# lidar4_sch.net
KiCad netlist of a schematic drawn in Altium Designer
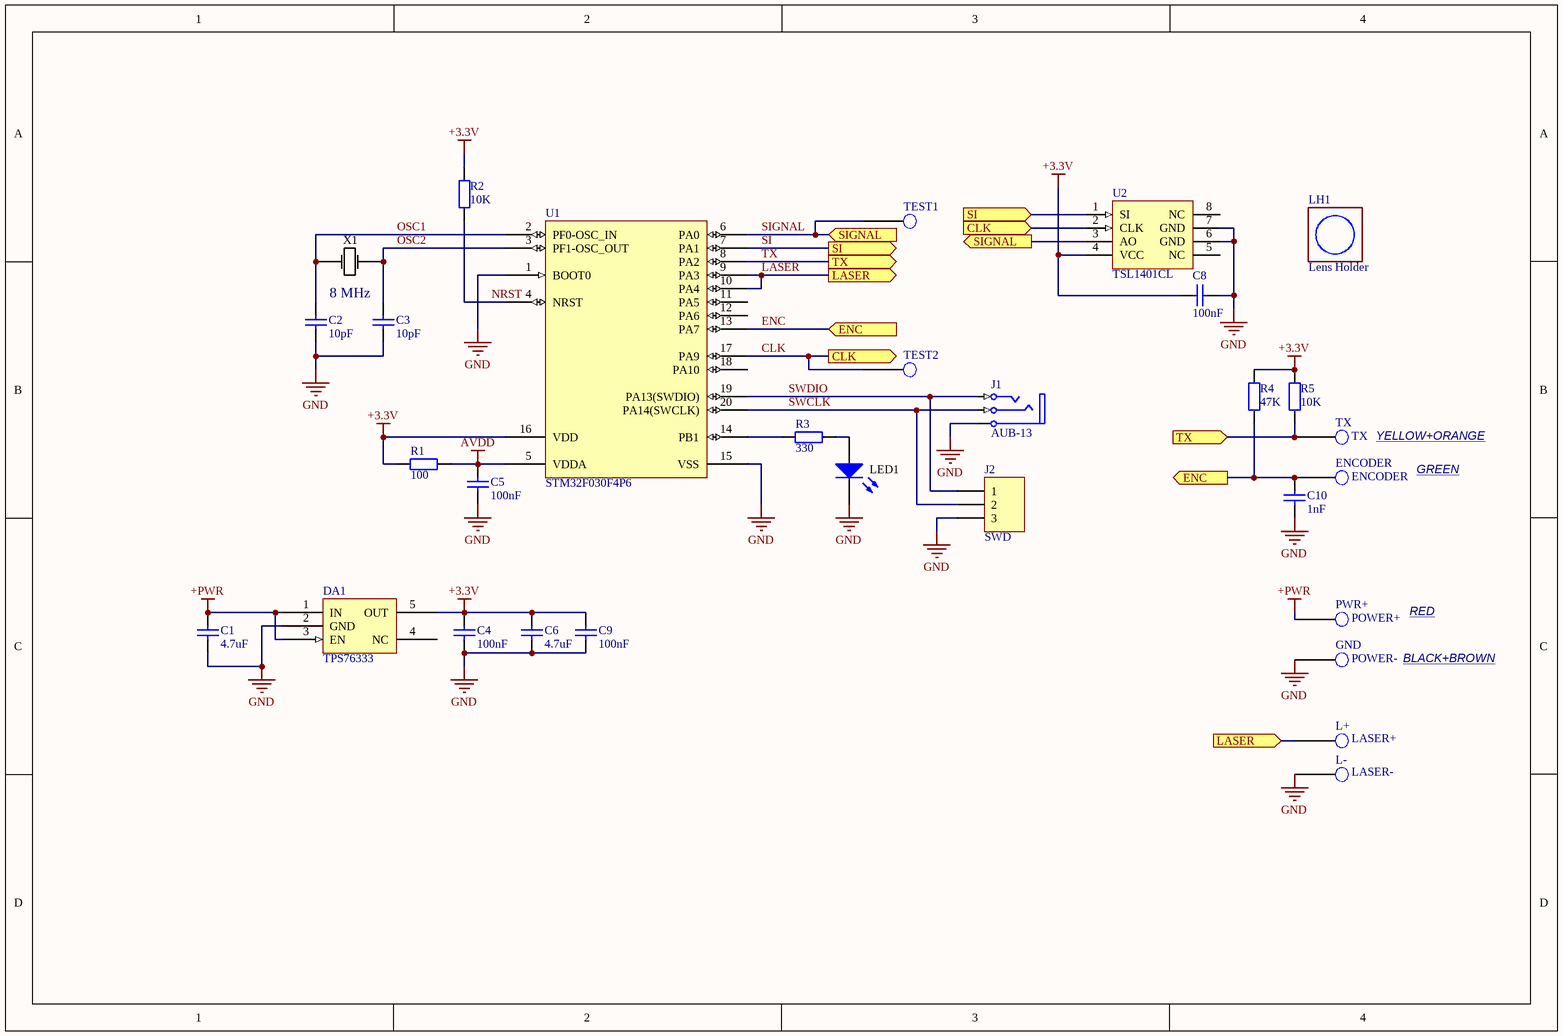
[diagram p0: lidar4_sch.SchDoc]

(export (version "E")
  (design (tool "Eeschema 10.0.6"))
  (components
    (comp (ref "C1")
      (value "4.7uF")
      (footprint "CAPC2012X135N")
      (description "Chip capacitor")
      (fields (field (name "VOLTAGE") "25V"))
      (libsource (lib "MyLibSch") (part "CC0805"))
    )
    (comp (ref "C2")
      (value "10pF")
      (footprint "CAPC1608X90N")
      (description "Chip capacitor")
      (fields (field (name "VOLTAGE") "25V"))
      (libsource (lib "MyLibSch") (part "CC0805"))
    )
    (comp (ref "C3")
      (value "10pF")
      (footprint "CAPC1608X90N")
      (description "Chip capacitor")
      (fields (field (name "VOLTAGE") "25V"))
      (libsource (lib "MyLibSch") (part "CC0805"))
    )
    (comp (ref "C4")
      (value "100nF")
      (footprint "CAPC1608X90N")
      (description "Chip capacitor")
      (fields (field (name "VOLTAGE") "25V"))
      (libsource (lib "MyLibSch") (part "CC0805"))
    )
    (comp (ref "C5")
      (value "100nF")
      (footprint "CAPC1608X90N")
      (description "Chip capacitor")
      (fields (field (name "VOLTAGE") "25V"))
      (libsource (lib "MyLibSch") (part "CC0805"))
    )
    (comp (ref "C6")
      (value "4.7uF")
      (footprint "CAPC2012X135N")
      (description "Chip capacitor")
      (fields (field (name "VOLTAGE") "25V"))
      (libsource (lib "MyLibSch") (part "CC0805"))
    )
    (comp (ref "C8")
      (value "100nF")
      (footprint "CAPC1608X90N")
      (description "Chip capacitor")
      (fields (field (name "VOLTAGE") "25V"))
      (libsource (lib "MyLibSch") (part "CC0805"))
    )
    (comp (ref "C9")
      (value "100nF")
      (footprint "CAPC1608X90N")
      (description "Chip capacitor")
      (fields (field (name "VOLTAGE") "25V"))
      (libsource (lib "MyLibSch") (part "CC0805"))
    )
    (comp (ref "C10")
      (value "1nF")
      (footprint "CAPC1608X90N")
      (description "Chip capacitor")
      (fields (field (name "VOLTAGE") "25V"))
      (libsource (lib "MyLibSch") (part "CC0805"))
    )
    (comp (ref "DA1")
      (value "TPS76333")
      (footprint "SOT23-5")
      (description "LDO")
      (libsource (lib "lcd_lib") (part "TPS76333"))
    )
    (comp (ref "ENCODER")
      (value "ENCODER")
      (footprint "Ext_pad")
      (description "Pad for wire")
      (libsource (lib "lcd_lib") (part "Ext Pad"))
    )
    (comp (ref "GND")
      (value "POWER-")
      (footprint "Ext_pad")
      (description "Pad for wire")
      (libsource (lib "lcd_lib") (part "Ext Pad"))
    )
    (comp (ref "J1")
      (value "AUB-13")
      (footprint "AUB-13")
      (description "Jack Socket, 1/4\" [6.5mm], Thru-Hole, Vertical, 3-Conductor Open Circuit (Non-Normalling)")
      (fields (field (name "PUBLISHER") "Altium Limited"))
      (libsource (lib "Miscellaneous Connectors") (part "Phonejack3"))
    )
    (comp (ref "J2")
      (value "SWD")
      (footprint "HDR1X3")
      (description "Header, 3-Pin")
      (fields (field (name "PUBLISHER") "Altium Limited"))
      (libsource (lib "Miscellaneous Connectors") (part "Header 3"))
    )
    (comp (ref "L+")
      (value "LASER+")
      (footprint "Ext_hole")
      (description "Pad for wire")
      (libsource (lib "lcd_lib") (part "Ext Pad"))
    )
    (comp (ref "L-")
      (value "LASER-")
      (footprint "Ext_hole")
      (description "Pad for wire")
      (libsource (lib "lcd_lib") (part "Ext Pad"))
    )
    (comp (ref "LED1")
      (value "LED")
      (footprint "PcbLib3:LED_0603")
      (description "LED_0603")
      (libsource (lib "lcd_lib") (part "LED_0603"))
    )
    (comp (ref "LH1")
      (value "Lens Holder")
      (footprint "LENS_HOLDER_2")
      (description "M12 Lens Holder")
      (libsource (lib "lcd_lib") (part "M12 Lens Holder"))
    )
    (comp (ref "PWR+")
      (value "POWER+")
      (footprint "Ext_pad")
      (description "Pad for wire")
      (libsource (lib "lcd_lib") (part "Ext Pad"))
    )
    (comp (ref "R1")
      (value "100")
      (footprint "RESC1608X55N")
      (description "Chip resistor")
      (fields (field (name "TOLERANCE") "5%"))
      (libsource (lib "") (part "RC0805_1"))
    )
    (comp (ref "R2")
      (value "10K")
      (footprint "RESC1608X55N")
      (description "Chip resistor")
      (fields (field (name "TOLERANCE") "5%"))
      (libsource (lib "MyLibSch") (part "RC0805"))
    )
    (comp (ref "R3")
      (value "330")
      (footprint "RESC1608X55N")
      (description "Chip resistor")
      (fields (field (name "TOLERANCE") "5%"))
      (libsource (lib "") (part "RC0805_2"))
    )
    (comp (ref "R4")
      (value "47K")
      (footprint "RESC1608X55N")
      (description "Chip resistor")
      (fields (field (name "TOLERANCE") "5%"))
      (libsource (lib "MyLibSch") (part "RC0805"))
    )
    (comp (ref "R5")
      (value "10K")
      (footprint "RESC1608X55N")
      (description "Chip resistor")
      (fields (field (name "TOLERANCE") "5%"))
      (libsource (lib "MyLibSch") (part "RC0805"))
    )
    (comp (ref "TEST1")
      (value "Pad")
      (footprint "PcbLib3:Ext_pad")
      (description "Pad for wire")
      (libsource (lib "lcd_lib") (part "Ext Pad"))
    )
    (comp (ref "TEST2")
      (value "Pad")
      (footprint "PcbLib3:Ext_pad")
      (description "Pad for wire")
      (libsource (lib "lcd_lib") (part "Ext Pad"))
    )
    (comp (ref "TX")
      (value "TX")
      (footprint "Ext_pad")
      (description "Pad for wire")
      (libsource (lib "lcd_lib") (part "Ext Pad"))
    )
    (comp (ref "U1")
      (value "STM32F030F4P6")
      (footprint "TSSOP65P640X120-20N")
      (libsource (lib "STM32 MCU") (part "STM32F030F4P6"))
    )
    (comp (ref "U2")
      (value "TSL1401CL")
      (footprint "PcbLib3:TSL1401CL_2")
      (description "Light sensor")
      (libsource (lib "lcd_lib") (part "TSL1401CL"))
    )
    (comp (ref "X1")
      (value "8 MHz")
      (footprint "SX-6 QUARTZ")
      (description "Quartz_SX-6 (SMD06035C4)")
      (fields (field (name "Comment") "Quartz"))
      (libsource (lib "lcd_lib") (part "Quartz_SX-6"))
    )
  )
  (nets
    (net (code "1") (name "+3.3V") (class "Default")
      (node (ref "C4") (pin "2") (pinfunction "2_2") (pintype "passive"))
      (node (ref "C6") (pin "2") (pinfunction "2_2") (pintype "passive"))
      (node (ref "C8") (pin "2") (pinfunction "2_2") (pintype "passive"))
      (node (ref "C9") (pin "2") (pinfunction "2_2") (pintype "passive"))
      (node (ref "DA1") (pin "5") (pinfunction "OUT_5") (pintype "passive"))
      (node (ref "R1") (pin "1") (pinfunction "1_1") (pintype "passive"))
      (node (ref "R2") (pin "1") (pinfunction "1_1") (pintype "passive"))
      (node (ref "R4") (pin "1") (pinfunction "1_1") (pintype "passive"))
      (node (ref "R5") (pin "1") (pinfunction "1_1") (pintype "passive"))
      (node (ref "U1") (pin "16") (pinfunction "VDD_16") (pintype "power_in"))
      (node (ref "U2") (pin "4") (pinfunction "VCC_4") (pintype "power_in"))
    )
    (net (code "2") (name "+PWR") (class "Default")
      (node (ref "C1") (pin "2") (pinfunction "2_2") (pintype "passive"))
      (node (ref "DA1") (pin "1") (pinfunction "IN_1") (pintype "power_in"))
      (node (ref "DA1") (pin "3") (pinfunction "EN_3") (pintype "input"))
      (node (ref "PWR+") (pin "1") (pinfunction "Pad_1") (pintype "passive"))
    )
    (net (code "3") (name "/CLK") (class "Default")
      (node (ref "TEST2") (pin "1") (pinfunction "Pad_1") (pintype "passive"))
      (node (ref "U1") (pin "17") (pinfunction "PA9_17") (pintype "bidirectional"))
      (node (ref "U2") (pin "2") (pinfunction "CLK_2") (pintype "input"))
    )
    (net (code "4") (name "/ENC") (class "Default")
      (node (ref "C10") (pin "2") (pinfunction "2_2") (pintype "passive"))
      (node (ref "ENCODER") (pin "1") (pinfunction "Pad_1") (pintype "passive"))
      (node (ref "R4") (pin "2") (pinfunction "2_2") (pintype "passive"))
      (node (ref "U1") (pin "13") (pinfunction "PA7_13") (pintype "bidirectional"))
    )
    (net (code "5") (name "/LASER") (class "Default")
      (node (ref "L+") (pin "1") (pinfunction "Pad_1") (pintype "passive"))
      (node (ref "U1") (pin "10") (pinfunction "PA4_10") (pintype "bidirectional"))
      (node (ref "U1") (pin "9") (pinfunction "PA3_9") (pintype "bidirectional"))
    )
    (net (code "6") (name "/NRST") (class "Default")
      (node (ref "R2") (pin "2") (pinfunction "2_2") (pintype "passive"))
      (node (ref "U1") (pin "4") (pinfunction "NRST_4") (pintype "bidirectional"))
    )
    (net (code "7") (name "/OSC1") (class "Default")
      (node (ref "C2") (pin "2") (pinfunction "2_2") (pintype "passive"))
      (node (ref "U1") (pin "2") (pinfunction "PF0-OSC_IN_2") (pintype "bidirectional"))
      (node (ref "X1") (pin "1") (pinfunction "1_1") (pintype "passive"))
    )
    (net (code "8") (name "/OSC2") (class "Default")
      (node (ref "C3") (pin "2") (pinfunction "2_2") (pintype "passive"))
      (node (ref "U1") (pin "3") (pinfunction "PF1-OSC_OUT_3") (pintype "bidirectional"))
      (node (ref "X1") (pin "3") (pinfunction "3_3") (pintype "passive"))
    )
    (net (code "9") (name "/SI") (class "Default")
      (node (ref "U1") (pin "7") (pinfunction "PA1_7") (pintype "bidirectional"))
      (node (ref "U2") (pin "1") (pinfunction "SI_1") (pintype "input"))
    )
    (net (code "10") (name "/SIGNAL") (class "Default")
      (node (ref "TEST1") (pin "1") (pinfunction "Pad_1") (pintype "passive"))
      (node (ref "U1") (pin "6") (pinfunction "PA0_6") (pintype "bidirectional"))
      (node (ref "U2") (pin "3") (pinfunction "AO_3") (pintype "passive"))
    )
    (net (code "11") (name "/SWCLK") (class "Default")
      (node (ref "J1") (pin "3") (pinfunction "R_3") (pintype "input"))
      (node (ref "J2") (pin "2") (pinfunction "2_2") (pintype "passive"))
      (node (ref "U1") (pin "20") (pinfunction "PA14(SWCLK)_20") (pintype "bidirectional"))
    )
    (net (code "12") (name "/SWDIO") (class "Default")
      (node (ref "J1") (pin "1") (pinfunction "T_1") (pintype "input"))
      (node (ref "J2") (pin "1") (pinfunction "1_1") (pintype "passive"))
      (node (ref "U1") (pin "19") (pinfunction "PA13(SWDIO)_19") (pintype "bidirectional"))
    )
    (net (code "13") (name "/TX") (class "Default")
      (node (ref "R5") (pin "2") (pinfunction "2_2") (pintype "passive"))
      (node (ref "TX") (pin "1") (pinfunction "Pad_1") (pintype "passive"))
      (node (ref "U1") (pin "8") (pinfunction "PA2_8") (pintype "bidirectional"))
    )
    (net (code "14") (name "AVDD") (class "Default")
      (node (ref "C5") (pin "2") (pinfunction "2_2") (pintype "passive"))
      (node (ref "R1") (pin "2") (pinfunction "2_2") (pintype "passive"))
      (node (ref "U1") (pin "5") (pinfunction "VDDA_5") (pintype "power_in"))
    )
    (net (code "15") (name "GND") (class "Default")
      (node (ref "C1") (pin "1") (pinfunction "1_1") (pintype "passive"))
      (node (ref "C10") (pin "1") (pinfunction "1_1") (pintype "passive"))
      (node (ref "C2") (pin "1") (pinfunction "1_1") (pintype "passive"))
      (node (ref "C3") (pin "1") (pinfunction "1_1") (pintype "passive"))
      (node (ref "C4") (pin "1") (pinfunction "1_1") (pintype "passive"))
      (node (ref "C5") (pin "1") (pinfunction "1_1") (pintype "passive"))
      (node (ref "C6") (pin "1") (pinfunction "1_1") (pintype "passive"))
      (node (ref "C8") (pin "1") (pinfunction "1_1") (pintype "passive"))
      (node (ref "C9") (pin "1") (pinfunction "1_1") (pintype "passive"))
      (node (ref "DA1") (pin "2") (pinfunction "GND_2") (pintype "power_in"))
      (node (ref "GND") (pin "1") (pinfunction "Pad_1") (pintype "passive"))
      (node (ref "J1") (pin "5") (pinfunction "S_5") (pintype "power_in"))
      (node (ref "J2") (pin "3") (pinfunction "3_3") (pintype "passive"))
      (node (ref "L-") (pin "1") (pinfunction "Pad_1") (pintype "passive"))
      (node (ref "LED1") (pin "2") (pinfunction "K_2") (pintype "passive"))
      (node (ref "U1") (pin "1") (pinfunction "BOOT0_1") (pintype "input"))
      (node (ref "U1") (pin "15") (pinfunction "VSS_15") (pintype "power_in"))
      (node (ref "U2") (pin "6") (pinfunction "GND_6") (pintype "power_in"))
      (node (ref "U2") (pin "7") (pinfunction "GND_7") (pintype "power_in"))
    )
    (net (code "16") (name "Net-(LED1-A)") (class "Default")
      (node (ref "LED1") (pin "1") (pinfunction "A_1") (pintype "passive"))
      (node (ref "R3") (pin "1") (pinfunction "1_1") (pintype "passive"))
    )
    (net (code "17") (name "Net-(U1-PB1)") (class "Default")
      (node (ref "R3") (pin "2") (pinfunction "2_2") (pintype "passive"))
      (node (ref "U1") (pin "14") (pinfunction "PB1_14") (pintype "bidirectional"))
    )
    (net (code "18") (name "unconnected-(DA1-NC-Pad4)") (class "Default")
      (node (ref "DA1") (pin "4") (pinfunction "NC_4") (pintype "passive"))
    )
    (net (code "19") (name "unconnected-(U1-PA5-Pad11)") (class "Default")
      (node (ref "U1") (pin "11") (pinfunction "PA5_11") (pintype "bidirectional"))
    )
    (net (code "20") (name "unconnected-(U1-PA6-Pad12)") (class "Default")
      (node (ref "U1") (pin "12") (pinfunction "PA6_12") (pintype "bidirectional"))
    )
    (net (code "21") (name "unconnected-(U1-PA10-Pad18)") (class "Default")
      (node (ref "U1") (pin "18") (pinfunction "PA10_18") (pintype "bidirectional"))
    )
    (net (code "22") (name "unconnected-(U2-NC-Pad5)") (class "Default")
      (node (ref "U2") (pin "5") (pinfunction "NC_5") (pintype "passive"))
    )
    (net (code "23") (name "unconnected-(U2-NC-Pad8)") (class "Default")
      (node (ref "U2") (pin "8") (pinfunction "NC_8") (pintype "passive"))
    )
  )
)
